# EdgeMax_MCU.net
KiCad netlist of a schematic drawn in Altium Designer
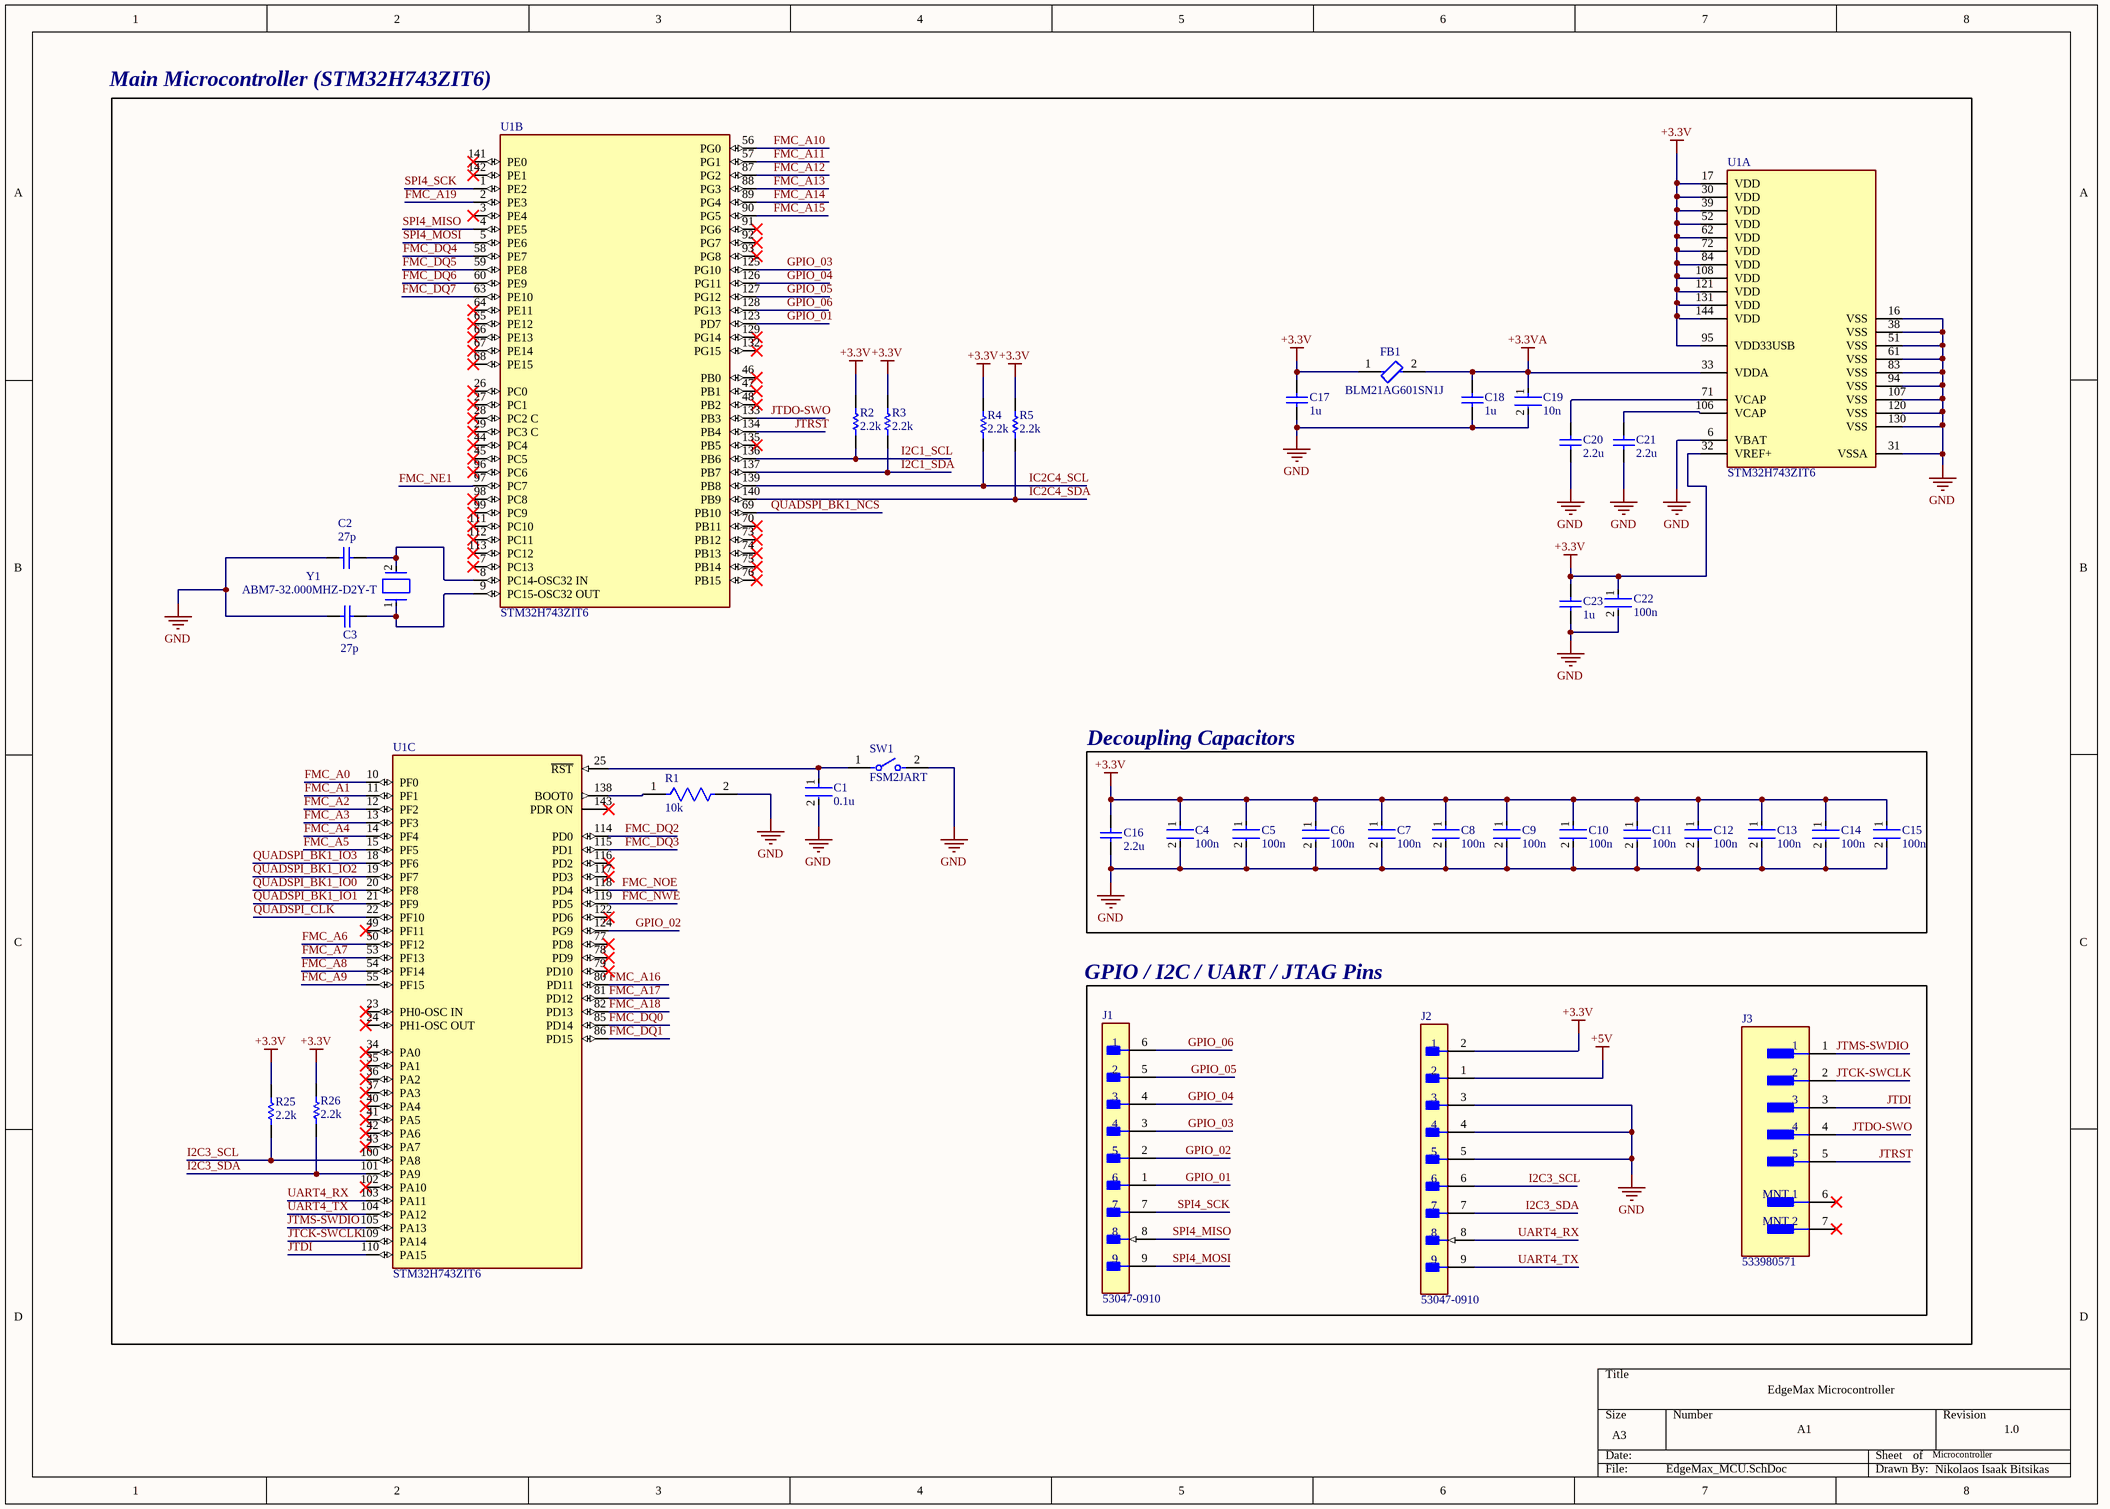
[diagram p0: EdgeMax_MCU.SchDoc]

(export (version "E")
  (design (tool "Eeschema 10.0.6"))
  (components
    (comp (ref "C1")
      (value "0.1u")
      (footprint "FP-C1206C-EB-MFG")
      (description "C1206 68,000 pF X7R 10.00% 50 V")
      (fields
        (field (name "MANUFACTURER") "KEMET")
        (field (name "OCTOPART") "https://octopart.com/c1206c683k5rac-kemet-1491650")
      )
      (libsource (lib "Altium Content Vault") (part "b4654b650e69147ec39a6b967a45e02"))
    )
    (comp (ref "C2")
      (value "27p")
      (footprint "CAPC1005X55X25LL05T10")
      (fields (field (name "PART NUMBER") "GRM1555C1H270JA01D") (field (name "MANUFACTURER") "Murata"))
      (libsource (lib "Altium Content Vault") (part "CAP"))
    )
    (comp (ref "C3")
      (value "27p")
      (footprint "CAPC1005X55X25LL05T10")
      (fields (field (name "PART NUMBER") "GRM1555C1H270JA01D") (field (name "MANUFACTURER") "Murata"))
      (libsource (lib "Altium Content Vault") (part "CAP"))
    )
    (comp (ref "C4")
      (value "100n")
      (footprint "FP-CL10-IPC_A")
      (description "Cap Ceramic 100nF 50V X7R ±10% Pad SMD 0603 +125°C T/R")
      (fields (field (name "VOLTAGE") "50V") (field (name "TOLERANCE") "10%"))
      (libsource (lib "Altium Content Vault") (part "b4654b650e69147ec39a6b967a45e02"))
    )
    (comp (ref "C5")
      (value "100n")
      (footprint "FP-CL10-IPC_A")
      (description "Cap Ceramic 100nF 50V X7R ±10% Pad SMD 0603 +125°C T/R")
      (fields (field (name "VOLTAGE") "50V") (field (name "TOLERANCE") "10%"))
      (libsource (lib "Altium Content Vault") (part "b4654b650e69147ec39a6b967a45e02"))
    )
    (comp (ref "C6")
      (value "100n")
      (footprint "FP-CL10-IPC_A")
      (description "Cap Ceramic 100nF 50V X7R ±10% Pad SMD 0603 +125°C T/R")
      (fields (field (name "VOLTAGE") "50V") (field (name "TOLERANCE") "10%"))
      (libsource (lib "Altium Content Vault") (part "b4654b650e69147ec39a6b967a45e02"))
    )
    (comp (ref "C7")
      (value "100n")
      (footprint "FP-CL10-IPC_A")
      (description "Cap Ceramic 100nF 50V X7R ±10% Pad SMD 0603 +125°C T/R")
      (fields (field (name "VOLTAGE") "50V") (field (name "TOLERANCE") "10%"))
      (libsource (lib "Altium Content Vault") (part "b4654b650e69147ec39a6b967a45e02"))
    )
    (comp (ref "C8")
      (value "100n")
      (footprint "FP-CL10-IPC_A")
      (description "Cap Ceramic 100nF 50V X7R ±10% Pad SMD 0603 +125°C T/R")
      (fields (field (name "VOLTAGE") "50V") (field (name "TOLERANCE") "10%"))
      (libsource (lib "Altium Content Vault") (part "b4654b650e69147ec39a6b967a45e02"))
    )
    (comp (ref "C9")
      (value "100n")
      (footprint "FP-CL10-IPC_A")
      (description "Cap Ceramic 100nF 50V X7R ±10% Pad SMD 0603 +125°C T/R")
      (fields (field (name "VOLTAGE") "50V") (field (name "TOLERANCE") "10%"))
      (libsource (lib "Altium Content Vault") (part "b4654b650e69147ec39a6b967a45e02"))
    )
    (comp (ref "C10")
      (value "100n")
      (footprint "FP-CL10-IPC_A")
      (description "Cap Ceramic 100nF 50V X7R ±10% Pad SMD 0603 +125°C T/R")
      (fields (field (name "VOLTAGE") "50V") (field (name "TOLERANCE") "10%"))
      (libsource (lib "Altium Content Vault") (part "b4654b650e69147ec39a6b967a45e02"))
    )
    (comp (ref "C11")
      (value "100n")
      (footprint "FP-CL10-IPC_A")
      (description "Cap Ceramic 100nF 50V X7R ±10% Pad SMD 0603 +125°C T/R")
      (fields (field (name "VOLTAGE") "50V") (field (name "TOLERANCE") "10%"))
      (libsource (lib "Altium Content Vault") (part "b4654b650e69147ec39a6b967a45e02"))
    )
    (comp (ref "C12")
      (value "100n")
      (footprint "FP-CL10-IPC_A")
      (description "Cap Ceramic 100nF 50V X7R ±10% Pad SMD 0603 +125°C T/R")
      (fields (field (name "VOLTAGE") "50V") (field (name "TOLERANCE") "10%"))
      (libsource (lib "Altium Content Vault") (part "b4654b650e69147ec39a6b967a45e02"))
    )
    (comp (ref "C13")
      (value "100n")
      (footprint "FP-CL10-IPC_A")
      (description "Cap Ceramic 100nF 50V X7R ±10% Pad SMD 0603 +125°C T/R")
      (fields (field (name "VOLTAGE") "50V") (field (name "TOLERANCE") "10%"))
      (libsource (lib "Altium Content Vault") (part "b4654b650e69147ec39a6b967a45e02"))
    )
    (comp (ref "C14")
      (value "100n")
      (footprint "FP-CL10-IPC_A")
      (description "Cap Ceramic 100nF 50V X7R ±10% Pad SMD 0603 +125°C T/R")
      (fields (field (name "VOLTAGE") "50V") (field (name "TOLERANCE") "10%"))
      (libsource (lib "Altium Content Vault") (part "b4654b650e69147ec39a6b967a45e02"))
    )
    (comp (ref "C15")
      (value "100n")
      (footprint "FP-CL10-IPC_A")
      (description "Cap Ceramic 100nF 50V X7R ±10% Pad SMD 0603 +125°C T/R")
      (fields (field (name "VOLTAGE") "50V") (field (name "TOLERANCE") "10%"))
      (libsource (lib "Altium Content Vault") (part "b4654b650e69147ec39a6b967a45e02"))
    )
    (comp (ref "C16")
      (value "2.2u")
      (footprint "CAPC2013X135X50ML10T20")
      (fields (field (name "MANUFACTURER") "Murata") (field (name "PART NUMBER") "GRM21BR71C225KA12L"))
      (libsource (lib "Altium Content Vault") (part "CAP"))
    )
    (comp (ref "C17")
      (value "1u")
      (footprint "CAPC2013X145X50LL20T25")
      (fields (field (name "MANUFACTURER") "Kemet") (field (name "PART NUMBER") "C0805C105K4PACTU"))
      (libsource (lib "Altium Content Vault") (part "CAP"))
    )
    (comp (ref "C18")
      (value "1u")
      (footprint "CAPC2013X145X50LL20T25")
      (fields (field (name "MANUFACTURER") "Kemet") (field (name "PART NUMBER") "C0805C105K4PACTU"))
      (libsource (lib "Altium Content Vault") (part "CAP"))
    )
    (comp (ref "C19")
      (value "10n")
      (footprint "FP-CC0402-MFG")
      (description "CC0402 10 nF X7R 10.00% 16 V")
      (fields
        (field (name "TOLERANCE") "0.1")
        (field (name "OCTOPART") "https://octopart.com/cc0402kpx7r7bb103-yageo-12885102")
      )
      (libsource (lib "Altium Content Vault") (part "11868f565c42a9108669ba33697ecf6"))
    )
    (comp (ref "C20")
      (value "2.2u")
      (footprint "CAPC2013X135X50ML10T20")
      (fields (field (name "MANUFACTURER") "Murata") (field (name "PART NUMBER") "GRM21BR71C225KA12L"))
      (libsource (lib "Altium Content Vault") (part "CAP"))
    )
    (comp (ref "C21")
      (value "2.2u")
      (footprint "CAPC2013X135X50ML10T20")
      (fields (field (name "MANUFACTURER") "Murata") (field (name "PART NUMBER") "GRM21BR71C225KA12L"))
      (libsource (lib "Altium Content Vault") (part "CAP"))
    )
    (comp (ref "C22")
      (value "100n")
      (footprint "FP-CL10-IPC_A")
      (description "Cap Ceramic 100nF 50V X7R ±10% Pad SMD 0603 +125°C T/R")
      (fields (field (name "VOLTAGE") "50V") (field (name "TOLERANCE") "10%"))
      (libsource (lib "Altium Content Vault") (part "b4654b650e69147ec39a6b967a45e02"))
    )
    (comp (ref "C23")
      (value "1u")
      (footprint "CAPC2013X145X50LL20T25")
      (fields (field (name "MANUFACTURER") "Kemet") (field (name "PART NUMBER") "C0805C105K4PACTU"))
      (libsource (lib "Altium Content Vault") (part "CAP"))
    )
    (comp (ref "FB1")
      (value "BLM21AG601SN1J")
      (footprint "FP-BLM21-0_2-t0_85-e0_5-IPC_A")
      (description "Chip Ferrite Bead, 0805, 600Ω @ 100MHz, 0.2Ω, 25%, 700mA")
      (fields (field (name "TOLERANCE") "25%"))
      (libsource (lib "Altium Content Vault") (part "5f30dd21d616792df468990f7003faa"))
    )
    (comp (ref "J1")
      (value "53047-0910")
      (footprint "FP-53047-0910-MFG")
      (description "CONN HEADER VERT 9POS 1.25MM")
      (libsource (lib "") (part "dac6df820644cf490af5575b4ac23d9_1"))
    )
    (comp (ref "J2")
      (value "53047-0910")
      (footprint "FP-53047-0910-MFG")
      (description "CONN HEADER VERT 9POS 1.25MM")
      (libsource (lib "Altium Content Vault") (part "dac6df820644cf490af5575b4ac23d9"))
    )
    (comp (ref "J3")
      (value "533980571")
      (footprint "FP-533980571-MFG")
      (description "CONN HEADER SMD 5POS 1.25MM")
      (fields
        (field (name "MANUFACTURER") "Molex")
        (field (name "OCTOPART") "https://octopart.com/53398-0571-molex-655292")
      )
      (libsource (lib "Altium Content Vault") (part "6850237a4f4b29aa870910a3747ee34"))
    )
    (comp (ref "R1")
      (value "10k")
      (footprint "FP-AC0603-MFG")
      (description "RES 10KΩ 1.00% 0.1W 0603")
      (fields (field (name "TOLERANCE") "1%"))
      (libsource (lib "Altium Content Vault") (part "1029c3af85768c4190bb7ad29bc67b5"))
    )
    (comp (ref "R2")
      (value "2.2k")
      (footprint "RESC1005X40X25LL05T05")
      (fields (field (name "MANUFACTURER") "Panasonic"))
      (libsource (lib "Altium Content Vault") (part "RES-2"))
    )
    (comp (ref "R3")
      (value "2.2k")
      (footprint "RESC1005X40X25LL05T05")
      (fields (field (name "MANUFACTURER") "Panasonic"))
      (libsource (lib "Altium Content Vault") (part "RES-2"))
    )
    (comp (ref "R4")
      (value "2.2k")
      (footprint "RESC1005X40X25LL05T05")
      (fields (field (name "MANUFACTURER") "Panasonic"))
      (libsource (lib "Altium Content Vault") (part "RES-2"))
    )
    (comp (ref "R5")
      (value "2.2k")
      (footprint "RESC1005X40X25LL05T05")
      (fields (field (name "MANUFACTURER") "Panasonic"))
      (libsource (lib "Altium Content Vault") (part "RES-2"))
    )
    (comp (ref "R25")
      (value "2.2k")
      (footprint "RESC1005X40X25LL05T05")
      (fields (field (name "MANUFACTURER") "Panasonic"))
      (libsource (lib "Altium Content Vault") (part "RES-2"))
    )
    (comp (ref "R26")
      (value "2.2k")
      (footprint "RESC1005X40X25LL05T05")
      (fields (field (name "MANUFACTURER") "Panasonic"))
      (libsource (lib "Altium Content Vault") (part "RES-2"))
    )
    (comp (ref "SW1")
      (value "FSM2JART")
      (footprint "FP-FSM2JART-MFG")
      (description "SWITCH TACTILE SPST-NO 0.05A 12V")
      (libsource (lib "Altium Content Vault") (part "bb27bde45df87f1f469753f287ef5ae"))
    )
    (comp (ref "U1")
      (value "STM32H743ZIT6")
      (footprint "FP-LQFP144-1A-MFG")
      (description "IC MCU 32BIT 2MB FLASH 144LQFP")
      (fields
        (field (name "MANUFACTURER") "STMicroelectronics")
        (field (name "OCTOPART") "https://octopart.com/stm32h743zit6-stmicroelectronics-76372529")
      )
      (libsource (lib "") (part "4977c5c7f8d170b58ef15f889e64ba1_2"))
    )
    (comp (ref "Y1")
      (value "ABM7-32.000MHZ-D2Y-T")
      (footprint "FP-ABM7-MFG")
      (description "Crystal 32MHz ±20ppm 18pF SMD-2 6mm x 3.5mm")
      (fields (field (name "TOLERANCE") "20ppm"))
      (libsource (lib "Altium Content Vault") (part "c23a69dc6c9e2f18f2079038eb95dd1"))
    )
  )
  (nets
    (net (code "1") (name "+3.3V") (class "Default")
      (node (ref "C10") (pin "1") (pinfunction "1_1") (pintype "passive"))
      (node (ref "C11") (pin "1") (pinfunction "1_1") (pintype "passive"))
      (node (ref "C12") (pin "1") (pinfunction "1_1") (pintype "passive"))
      (node (ref "C13") (pin "1") (pinfunction "1_1") (pintype "passive"))
      (node (ref "C14") (pin "1") (pinfunction "1_1") (pintype "passive"))
      (node (ref "C15") (pin "1") (pinfunction "1_1") (pintype "passive"))
      (node (ref "C16") (pin "2") (pinfunction "2_2") (pintype "passive"))
      (node (ref "C17") (pin "2") (pinfunction "2_2") (pintype "passive"))
      (node (ref "C22") (pin "1") (pinfunction "1_1") (pintype "passive"))
      (node (ref "C23") (pin "2") (pinfunction "2_2") (pintype "passive"))
      (node (ref "C4") (pin "1") (pinfunction "1_1") (pintype "passive"))
      (node (ref "C5") (pin "1") (pinfunction "1_1") (pintype "passive"))
      (node (ref "C6") (pin "1") (pinfunction "1_1") (pintype "passive"))
      (node (ref "C7") (pin "1") (pinfunction "1_1") (pintype "passive"))
      (node (ref "C8") (pin "1") (pinfunction "1_1") (pintype "passive"))
      (node (ref "C9") (pin "1") (pinfunction "1_1") (pintype "passive"))
      (node (ref "FB1") (pin "1") (pinfunction "1_1") (pintype "passive"))
      (node (ref "J2") (pin "2") (pinfunction "2_2") (pintype "passive"))
      (node (ref "R2") (pin "2") (pinfunction "2_2") (pintype "passive"))
      (node (ref "R25") (pin "2") (pinfunction "2_2") (pintype "passive"))
      (node (ref "R26") (pin "2") (pinfunction "2_2") (pintype "passive"))
      (node (ref "R3") (pin "2") (pinfunction "2_2") (pintype "passive"))
      (node (ref "R4") (pin "2") (pinfunction "2_2") (pintype "passive"))
      (node (ref "R5") (pin "2") (pinfunction "2_2") (pintype "passive"))
      (node (ref "U1") (pin "108") (pinfunction "VDD_108") (pintype "power_in"))
      (node (ref "U1") (pin "121") (pinfunction "VDD_121") (pintype "power_in"))
      (node (ref "U1") (pin "131") (pinfunction "VDD_131") (pintype "power_in"))
      (node (ref "U1") (pin "144") (pinfunction "VDD_144") (pintype "power_in"))
      (node (ref "U1") (pin "17") (pinfunction "VDD_17") (pintype "power_in"))
      (node (ref "U1") (pin "30") (pinfunction "VDD_30") (pintype "power_in"))
      (node (ref "U1") (pin "32") (pinfunction "VREF+_32") (pintype "power_in"))
      (node (ref "U1") (pin "39") (pinfunction "VDD_39") (pintype "power_in"))
      (node (ref "U1") (pin "52") (pinfunction "VDD_52") (pintype "power_in"))
      (node (ref "U1") (pin "62") (pinfunction "VDD_62") (pintype "power_in"))
      (node (ref "U1") (pin "72") (pinfunction "VDD_72") (pintype "power_in"))
      (node (ref "U1") (pin "84") (pinfunction "VDD_84") (pintype "power_in"))
      (node (ref "U1") (pin "95") (pinfunction "VDD33USB_95") (pintype "power_in"))
    )
    (net (code "2") (name "+3.3VA") (class "Default")
      (node (ref "C18") (pin "2") (pinfunction "2_2") (pintype "passive"))
      (node (ref "C19") (pin "1") (pinfunction "1_1") (pintype "passive"))
      (node (ref "FB1") (pin "2") (pinfunction "2_2") (pintype "passive"))
      (node (ref "U1") (pin "33") (pinfunction "VDDA_33") (pintype "power_in"))
    )
    (net (code "3") (name "+5V") (class "Default")
      (node (ref "J2") (pin "1") (pinfunction "1_1") (pintype "passive"))
    )
    (net (code "4") (name "/FMC_A0") (class "Default")
      (node (ref "U1") (pin "10") (pinfunction "PF0_10") (pintype "bidirectional"))
    )
    (net (code "5") (name "/FMC_A1") (class "Default")
      (node (ref "U1") (pin "11") (pinfunction "PF1_11") (pintype "bidirectional"))
    )
    (net (code "6") (name "/FMC_A2") (class "Default")
      (node (ref "U1") (pin "12") (pinfunction "PF2_12") (pintype "bidirectional"))
    )
    (net (code "7") (name "/FMC_A3") (class "Default")
      (node (ref "U1") (pin "13") (pinfunction "PF3_13") (pintype "bidirectional"))
    )
    (net (code "8") (name "/FMC_A4") (class "Default")
      (node (ref "U1") (pin "14") (pinfunction "PF4_14") (pintype "bidirectional"))
    )
    (net (code "9") (name "/FMC_A5") (class "Default")
      (node (ref "U1") (pin "15") (pinfunction "PF5_15") (pintype "bidirectional"))
    )
    (net (code "10") (name "/FMC_A6") (class "Default")
      (node (ref "U1") (pin "50") (pinfunction "PF12_50") (pintype "bidirectional"))
    )
    (net (code "11") (name "/FMC_A7") (class "Default")
      (node (ref "U1") (pin "53") (pinfunction "PF13_53") (pintype "bidirectional"))
    )
    (net (code "12") (name "/FMC_A8") (class "Default")
      (node (ref "U1") (pin "54") (pinfunction "PF14_54") (pintype "bidirectional"))
    )
    (net (code "13") (name "/FMC_A9") (class "Default")
      (node (ref "U1") (pin "55") (pinfunction "PF15_55") (pintype "bidirectional"))
    )
    (net (code "14") (name "/FMC_A10") (class "Default")
      (node (ref "U1") (pin "56") (pinfunction "PG0_56") (pintype "bidirectional"))
    )
    (net (code "15") (name "/FMC_A11") (class "Default")
      (node (ref "U1") (pin "57") (pinfunction "PG1_57") (pintype "bidirectional"))
    )
    (net (code "16") (name "/FMC_A12") (class "Default")
      (node (ref "U1") (pin "87") (pinfunction "PG2_87") (pintype "bidirectional"))
    )
    (net (code "17") (name "/FMC_A13") (class "Default")
      (node (ref "U1") (pin "88") (pinfunction "PG3_88") (pintype "bidirectional"))
    )
    (net (code "18") (name "/FMC_A14") (class "Default")
      (node (ref "U1") (pin "89") (pinfunction "PG4_89") (pintype "bidirectional"))
    )
    (net (code "19") (name "/FMC_A15") (class "Default")
      (node (ref "U1") (pin "90") (pinfunction "PG5_90") (pintype "bidirectional"))
    )
    (net (code "20") (name "/FMC_A16") (class "Default")
      (node (ref "U1") (pin "80") (pinfunction "PD11_80") (pintype "bidirectional"))
    )
    (net (code "21") (name "/FMC_A17") (class "Default")
      (node (ref "U1") (pin "81") (pinfunction "PD12_81") (pintype "bidirectional"))
    )
    (net (code "22") (name "/FMC_A18") (class "Default")
      (node (ref "U1") (pin "82") (pinfunction "PD13_82") (pintype "bidirectional"))
    )
    (net (code "23") (name "/FMC_A19") (class "Default")
      (node (ref "U1") (pin "2") (pinfunction "PE3_2") (pintype "bidirectional"))
    )
    (net (code "24") (name "/FMC_DQ0") (class "Default")
      (node (ref "U1") (pin "85") (pinfunction "PD14_85") (pintype "bidirectional"))
    )
    (net (code "25") (name "/FMC_DQ1") (class "Default")
      (node (ref "U1") (pin "86") (pinfunction "PD15_86") (pintype "bidirectional"))
    )
    (net (code "26") (name "/FMC_DQ2") (class "Default")
      (node (ref "U1") (pin "114") (pinfunction "PD0_114") (pintype "bidirectional"))
    )
    (net (code "27") (name "/FMC_DQ3") (class "Default")
      (node (ref "U1") (pin "115") (pinfunction "PD1_115") (pintype "bidirectional"))
    )
    (net (code "28") (name "/FMC_DQ4") (class "Default")
      (node (ref "U1") (pin "58") (pinfunction "PE7_58") (pintype "bidirectional"))
    )
    (net (code "29") (name "/FMC_DQ5") (class "Default")
      (node (ref "U1") (pin "59") (pinfunction "PE8_59") (pintype "bidirectional"))
    )
    (net (code "30") (name "/FMC_DQ6") (class "Default")
      (node (ref "U1") (pin "60") (pinfunction "PE9_60") (pintype "bidirectional"))
    )
    (net (code "31") (name "/FMC_DQ7") (class "Default")
      (node (ref "U1") (pin "63") (pinfunction "PE10_63") (pintype "bidirectional"))
    )
    (net (code "32") (name "/FMC_NOE") (class "Default")
      (node (ref "U1") (pin "118") (pinfunction "PD4_118") (pintype "bidirectional"))
    )
    (net (code "33") (name "/FMC_NWE") (class "Default")
      (node (ref "U1") (pin "119") (pinfunction "PD5_119") (pintype "bidirectional"))
    )
    (net (code "34") (name "/FMC_ΝΕ1") (class "Default")
      (node (ref "U1") (pin "97") (pinfunction "PC7_97") (pintype "bidirectional"))
    )
    (net (code "35") (name "/GPIO_01") (class "Default")
      (node (ref "J1") (pin "1") (pinfunction "1_1") (pintype "passive"))
      (node (ref "U1") (pin "123") (pinfunction "PD7_123") (pintype "bidirectional"))
    )
    (net (code "36") (name "/GPIO_02") (class "Default")
      (node (ref "J1") (pin "2") (pinfunction "2_2") (pintype "passive"))
      (node (ref "U1") (pin "124") (pinfunction "PG9_124") (pintype "bidirectional"))
    )
    (net (code "37") (name "/GPIO_03") (class "Default")
      (node (ref "J1") (pin "3") (pinfunction "3_3") (pintype "passive"))
      (node (ref "U1") (pin "125") (pinfunction "PG10_125") (pintype "bidirectional"))
    )
    (net (code "38") (name "/GPIO_04") (class "Default")
      (node (ref "J1") (pin "4") (pinfunction "4_4") (pintype "passive"))
      (node (ref "U1") (pin "126") (pinfunction "PG11_126") (pintype "bidirectional"))
    )
    (net (code "39") (name "/GPIO_05") (class "Default")
      (node (ref "J1") (pin "5") (pinfunction "5_5") (pintype "passive"))
      (node (ref "U1") (pin "127") (pinfunction "PG12_127") (pintype "bidirectional"))
    )
    (net (code "40") (name "/GPIO_06") (class "Default")
      (node (ref "J1") (pin "6") (pinfunction "6_6") (pintype "passive"))
      (node (ref "U1") (pin "128") (pinfunction "PG13_128") (pintype "bidirectional"))
    )
    (net (code "41") (name "/I2C1_SCL") (class "Default")
      (node (ref "R2") (pin "1") (pinfunction "1_1") (pintype "passive"))
      (node (ref "U1") (pin "136") (pinfunction "PB6_136") (pintype "bidirectional"))
    )
    (net (code "42") (name "/I2C1_SDA") (class "Default")
      (node (ref "R3") (pin "1") (pinfunction "1_1") (pintype "passive"))
      (node (ref "U1") (pin "137") (pinfunction "PB7_137") (pintype "bidirectional"))
    )
    (net (code "43") (name "/I2C3_SCL") (class "Default")
      (node (ref "J2") (pin "6") (pinfunction "6_6") (pintype "passive"))
      (node (ref "R25") (pin "1") (pinfunction "1_1") (pintype "passive"))
      (node (ref "U1") (pin "100") (pinfunction "PA8_100") (pintype "bidirectional"))
    )
    (net (code "44") (name "/I2C3_SDA") (class "Default")
      (node (ref "J2") (pin "7") (pinfunction "7_7") (pintype "passive"))
      (node (ref "R26") (pin "1") (pinfunction "1_1") (pintype "passive"))
      (node (ref "U1") (pin "101") (pinfunction "PA9_101") (pintype "bidirectional"))
    )
    (net (code "45") (name "/IC2C4_SCL") (class "Default")
      (node (ref "R4") (pin "1") (pinfunction "1_1") (pintype "passive"))
      (node (ref "U1") (pin "139") (pinfunction "PB8_139") (pintype "bidirectional"))
    )
    (net (code "46") (name "/IC2C4_SDA") (class "Default")
      (node (ref "R5") (pin "1") (pinfunction "1_1") (pintype "passive"))
      (node (ref "U1") (pin "140") (pinfunction "PB9_140") (pintype "bidirectional"))
    )
    (net (code "47") (name "/JTCK-SWCLK") (class "Default")
      (node (ref "J3") (pin "2") (pinfunction "2_2") (pintype "passive"))
      (node (ref "U1") (pin "109") (pinfunction "PA14_109") (pintype "bidirectional"))
    )
    (net (code "48") (name "/JTDI") (class "Default")
      (node (ref "J3") (pin "3") (pinfunction "3_3") (pintype "passive"))
      (node (ref "U1") (pin "110") (pinfunction "PA15_110") (pintype "bidirectional"))
    )
    (net (code "49") (name "/JTDO-SWO") (class "Default")
      (node (ref "J3") (pin "4") (pinfunction "4_4") (pintype "passive"))
      (node (ref "U1") (pin "133") (pinfunction "PB3_133") (pintype "bidirectional"))
    )
    (net (code "50") (name "/JTMS-SWDIO") (class "Default")
      (node (ref "J3") (pin "1") (pinfunction "1_1") (pintype "passive"))
      (node (ref "U1") (pin "105") (pinfunction "PA13_105") (pintype "bidirectional"))
    )
    (net (code "51") (name "/JTRST") (class "Default")
      (node (ref "J3") (pin "5") (pinfunction "5_5") (pintype "passive"))
      (node (ref "U1") (pin "134") (pinfunction "PB4_134") (pintype "bidirectional"))
    )
    (net (code "52") (name "/QUADSPI_BK1_IO0") (class "Default")
      (node (ref "U1") (pin "20") (pinfunction "PF8_20") (pintype "bidirectional"))
    )
    (net (code "53") (name "/QUADSPI_BK1_IO1") (class "Default")
      (node (ref "U1") (pin "21") (pinfunction "PF9_21") (pintype "bidirectional"))
    )
    (net (code "54") (name "/QUADSPI_BK1_IO2") (class "Default")
      (node (ref "U1") (pin "19") (pinfunction "PF7_19") (pintype "bidirectional"))
    )
    (net (code "55") (name "/QUADSPI_BK1_IO3") (class "Default")
      (node (ref "U1") (pin "18") (pinfunction "PF6_18") (pintype "bidirectional"))
    )
    (net (code "56") (name "/QUADSPI_BK1_NCS") (class "Default")
      (node (ref "U1") (pin "69") (pinfunction "PB10_69") (pintype "bidirectional"))
    )
    (net (code "57") (name "/QUADSPI_CLK") (class "Default")
      (node (ref "U1") (pin "22") (pinfunction "PF10_22") (pintype "bidirectional"))
    )
    (net (code "58") (name "/SPI4_MISO") (class "Default")
      (node (ref "J1") (pin "8") (pinfunction "8_8") (pintype "input"))
      (node (ref "U1") (pin "4") (pinfunction "PE5_4") (pintype "bidirectional"))
    )
    (net (code "59") (name "/SPI4_MOSI") (class "Default")
      (node (ref "J1") (pin "9") (pinfunction "9_9") (pintype "passive"))
      (node (ref "U1") (pin "5") (pinfunction "PE6_5") (pintype "bidirectional"))
    )
    (net (code "60") (name "/SPI4_SCK") (class "Default")
      (node (ref "J1") (pin "7") (pinfunction "7_7") (pintype "passive"))
      (node (ref "U1") (pin "1") (pinfunction "PE2_1") (pintype "bidirectional"))
    )
    (net (code "61") (name "/UART4_RX") (class "Default")
      (node (ref "J2") (pin "8") (pinfunction "8_8") (pintype "input"))
      (node (ref "U1") (pin "103") (pinfunction "PA11_103") (pintype "bidirectional"))
    )
    (net (code "62") (name "/UART4_TX") (class "Default")
      (node (ref "J2") (pin "9") (pinfunction "9_9") (pintype "passive"))
      (node (ref "U1") (pin "104") (pinfunction "PA12_104") (pintype "bidirectional"))
    )
    (net (code "63") (name "GND") (class "Default")
      (node (ref "C1") (pin "2") (pinfunction "2_2") (pintype "passive"))
      (node (ref "C10") (pin "2") (pinfunction "2_2") (pintype "passive"))
      (node (ref "C11") (pin "2") (pinfunction "2_2") (pintype "passive"))
      (node (ref "C12") (pin "2") (pinfunction "2_2") (pintype "passive"))
      (node (ref "C13") (pin "2") (pinfunction "2_2") (pintype "passive"))
      (node (ref "C14") (pin "2") (pinfunction "2_2") (pintype "passive"))
      (node (ref "C15") (pin "2") (pinfunction "2_2") (pintype "passive"))
      (node (ref "C16") (pin "1") (pinfunction "1_1") (pintype "passive"))
      (node (ref "C17") (pin "1") (pinfunction "1_1") (pintype "passive"))
      (node (ref "C18") (pin "1") (pinfunction "1_1") (pintype "passive"))
      (node (ref "C19") (pin "2") (pinfunction "2_2") (pintype "passive"))
      (node (ref "C2") (pin "2") (pinfunction "2_2") (pintype "passive"))
      (node (ref "C20") (pin "1") (pinfunction "1_1") (pintype "passive"))
      (node (ref "C21") (pin "1") (pinfunction "1_1") (pintype "passive"))
      (node (ref "C22") (pin "2") (pinfunction "2_2") (pintype "passive"))
      (node (ref "C23") (pin "1") (pinfunction "1_1") (pintype "passive"))
      (node (ref "C3") (pin "1") (pinfunction "1_1") (pintype "passive"))
      (node (ref "C4") (pin "2") (pinfunction "2_2") (pintype "passive"))
      (node (ref "C5") (pin "2") (pinfunction "2_2") (pintype "passive"))
      (node (ref "C6") (pin "2") (pinfunction "2_2") (pintype "passive"))
      (node (ref "C7") (pin "2") (pinfunction "2_2") (pintype "passive"))
      (node (ref "C8") (pin "2") (pinfunction "2_2") (pintype "passive"))
      (node (ref "C9") (pin "2") (pinfunction "2_2") (pintype "passive"))
      (node (ref "J2") (pin "3") (pinfunction "3_3") (pintype "passive"))
      (node (ref "J2") (pin "4") (pinfunction "4_4") (pintype "passive"))
      (node (ref "J2") (pin "5") (pinfunction "5_5") (pintype "passive"))
      (node (ref "R1") (pin "2") (pinfunction "2_2") (pintype "passive"))
      (node (ref "SW1") (pin "2") (pinfunction "2_2") (pintype "passive"))
      (node (ref "U1") (pin "107") (pinfunction "VSS_107") (pintype "power_in"))
      (node (ref "U1") (pin "120") (pinfunction "VSS_120") (pintype "power_in"))
      (node (ref "U1") (pin "130") (pinfunction "VSS_130") (pintype "power_in"))
      (node (ref "U1") (pin "16") (pinfunction "VSS_16") (pintype "power_in"))
      (node (ref "U1") (pin "31") (pinfunction "VSSA_31") (pintype "power_in"))
      (node (ref "U1") (pin "38") (pinfunction "VSS_38") (pintype "power_in"))
      (node (ref "U1") (pin "51") (pinfunction "VSS_51") (pintype "power_in"))
      (node (ref "U1") (pin "6") (pinfunction "VBAT_6") (pintype "power_in"))
      (node (ref "U1") (pin "61") (pinfunction "VSS_61") (pintype "power_in"))
      (node (ref "U1") (pin "83") (pinfunction "VSS_83") (pintype "power_in"))
      (node (ref "U1") (pin "94") (pinfunction "VSS_94") (pintype "power_in"))
    )
    (net (code "64") (name "Net-(C20-Pad2)") (class "Default")
      (node (ref "C20") (pin "2") (pinfunction "2_2") (pintype "passive"))
      (node (ref "U1") (pin "71") (pinfunction "VCAP_71") (pintype "power_in"))
    )
    (net (code "65") (name "Net-(C21-Pad2)") (class "Default")
      (node (ref "C21") (pin "2") (pinfunction "2_2") (pintype "passive"))
      (node (ref "U1") (pin "106") (pinfunction "VCAP_106") (pintype "power_in"))
    )
    (net (code "66") (name "Net-(U1B-PC14-OSC32_IN)") (class "Default")
      (node (ref "C2") (pin "1") (pinfunction "1_1") (pintype "passive"))
      (node (ref "U1") (pin "8") (pinfunction "PC14-OSC32_IN_8") (pintype "bidirectional"))
      (node (ref "Y1") (pin "2") (pinfunction "2_2") (pintype "passive"))
    )
    (net (code "67") (name "Net-(U1B-PC15-OSC32_OUT)") (class "Default")
      (node (ref "C3") (pin "2") (pinfunction "2_2") (pintype "passive"))
      (node (ref "U1") (pin "9") (pinfunction "PC15-OSC32_OUT_9") (pintype "bidirectional"))
      (node (ref "Y1") (pin "1") (pinfunction "1_1") (pintype "passive"))
    )
    (net (code "68") (name "Net-(U1C-BOOT0)") (class "Default")
      (node (ref "R1") (pin "1") (pinfunction "1_1") (pintype "passive"))
      (node (ref "U1") (pin "138") (pinfunction "BOOT0_138") (pintype "output"))
    )
    (net (code "69") (name "Net-(U1C-~{RST})") (class "Default")
      (node (ref "C1") (pin "1") (pinfunction "1_1") (pintype "passive"))
      (node (ref "SW1") (pin "1") (pinfunction "1_1") (pintype "passive"))
      (node (ref "U1") (pin "25") (pinfunction "~{RST}_25") (pintype "input"))
    )
    (net (code "70") (name "unconnected-(J3-MNT_1-Pad6)") (class "Default")
      (node (ref "J3") (pin "6") (pinfunction "MNT_1_6") (pintype "passive+no_connect"))
    )
    (net (code "71") (name "unconnected-(J3-MNT_2-Pad7)") (class "Default")
      (node (ref "J3") (pin "7") (pinfunction "MNT_2_7") (pintype "passive+no_connect"))
    )
    (net (code "72") (name "unconnected-(U1B-PB0-Pad46)") (class "Default")
      (node (ref "U1") (pin "46") (pinfunction "PB0_46") (pintype "bidirectional+no_connect"))
    )
    (net (code "73") (name "unconnected-(U1B-PB1-Pad47)") (class "Default")
      (node (ref "U1") (pin "47") (pinfunction "PB1_47") (pintype "bidirectional+no_connect"))
    )
    (net (code "74") (name "unconnected-(U1B-PB2-Pad48)") (class "Default")
      (node (ref "U1") (pin "48") (pinfunction "PB2_48") (pintype "bidirectional+no_connect"))
    )
    (net (code "75") (name "unconnected-(U1B-PB5-Pad135)") (class "Default")
      (node (ref "U1") (pin "135") (pinfunction "PB5_135") (pintype "bidirectional+no_connect"))
    )
    (net (code "76") (name "unconnected-(U1B-PB11-Pad70)") (class "Default")
      (node (ref "U1") (pin "70") (pinfunction "PB11_70") (pintype "bidirectional+no_connect"))
    )
    (net (code "77") (name "unconnected-(U1B-PB12-Pad73)") (class "Default")
      (node (ref "U1") (pin "73") (pinfunction "PB12_73") (pintype "bidirectional+no_connect"))
    )
    (net (code "78") (name "unconnected-(U1B-PB13-Pad74)") (class "Default")
      (node (ref "U1") (pin "74") (pinfunction "PB13_74") (pintype "bidirectional+no_connect"))
    )
    (net (code "79") (name "unconnected-(U1B-PB14-Pad75)") (class "Default")
      (node (ref "U1") (pin "75") (pinfunction "PB14_75") (pintype "bidirectional+no_connect"))
    )
    (net (code "80") (name "unconnected-(U1B-PB15-Pad76)") (class "Default")
      (node (ref "U1") (pin "76") (pinfunction "PB15_76") (pintype "bidirectional+no_connect"))
    )
    (net (code "81") (name "unconnected-(U1B-PC0-Pad26)") (class "Default")
      (node (ref "U1") (pin "26") (pinfunction "PC0_26") (pintype "bidirectional+no_connect"))
    )
    (net (code "82") (name "unconnected-(U1B-PC1-Pad27)") (class "Default")
      (node (ref "U1") (pin "27") (pinfunction "PC1_27") (pintype "bidirectional+no_connect"))
    )
    (net (code "83") (name "unconnected-(U1B-PC2_C-Pad28)") (class "Default")
      (node (ref "U1") (pin "28") (pinfunction "PC2_C_28") (pintype "bidirectional+no_connect"))
    )
    (net (code "84") (name "unconnected-(U1B-PC3_C-Pad29)") (class "Default")
      (node (ref "U1") (pin "29") (pinfunction "PC3_C_29") (pintype "bidirectional+no_connect"))
    )
    (net (code "85") (name "unconnected-(U1B-PC4-Pad44)") (class "Default")
      (node (ref "U1") (pin "44") (pinfunction "PC4_44") (pintype "bidirectional+no_connect"))
    )
    (net (code "86") (name "unconnected-(U1B-PC5-Pad45)") (class "Default")
      (node (ref "U1") (pin "45") (pinfunction "PC5_45") (pintype "bidirectional+no_connect"))
    )
    (net (code "87") (name "unconnected-(U1B-PC6-Pad96)") (class "Default")
      (node (ref "U1") (pin "96") (pinfunction "PC6_96") (pintype "bidirectional+no_connect"))
    )
    (net (code "88") (name "unconnected-(U1B-PC8-Pad98)") (class "Default")
      (node (ref "U1") (pin "98") (pinfunction "PC8_98") (pintype "bidirectional+no_connect"))
    )
    (net (code "89") (name "unconnected-(U1B-PC9-Pad99)") (class "Default")
      (node (ref "U1") (pin "99") (pinfunction "PC9_99") (pintype "bidirectional+no_connect"))
    )
    (net (code "90") (name "unconnected-(U1B-PC10-Pad111)") (class "Default")
      (node (ref "U1") (pin "111") (pinfunction "PC10_111") (pintype "bidirectional+no_connect"))
    )
    (net (code "91") (name "unconnected-(U1B-PC11-Pad112)") (class "Default")
      (node (ref "U1") (pin "112") (pinfunction "PC11_112") (pintype "bidirectional+no_connect"))
    )
    (net (code "92") (name "unconnected-(U1B-PC12-Pad113)") (class "Default")
      (node (ref "U1") (pin "113") (pinfunction "PC12_113") (pintype "bidirectional+no_connect"))
    )
    (net (code "93") (name "unconnected-(U1B-PC13-Pad7)") (class "Default")
      (node (ref "U1") (pin "7") (pinfunction "PC13_7") (pintype "bidirectional+no_connect"))
    )
    (net (code "94") (name "unconnected-(U1B-PE0-Pad141)") (class "Default")
      (node (ref "U1") (pin "141") (pinfunction "PE0_141") (pintype "bidirectional+no_connect"))
    )
    (net (code "95") (name "unconnected-(U1B-PE1-Pad142)") (class "Default")
      (node (ref "U1") (pin "142") (pinfunction "PE1_142") (pintype "bidirectional+no_connect"))
    )
    (net (code "96") (name "unconnected-(U1B-PE4-Pad3)") (class "Default")
      (node (ref "U1") (pin "3") (pinfunction "PE4_3") (pintype "bidirectional+no_connect"))
    )
    (net (code "97") (name "unconnected-(U1B-PE11-Pad64)") (class "Default")
      (node (ref "U1") (pin "64") (pinfunction "PE11_64") (pintype "bidirectional+no_connect"))
    )
    (net (code "98") (name "unconnected-(U1B-PE12-Pad65)") (class "Default")
      (node (ref "U1") (pin "65") (pinfunction "PE12_65") (pintype "bidirectional+no_connect"))
    )
    (net (code "99") (name "unconnected-(U1B-PE13-Pad66)") (class "Default")
      (node (ref "U1") (pin "66") (pinfunction "PE13_66") (pintype "bidirectional+no_connect"))
    )
    (net (code "100") (name "unconnected-(U1B-PE14-Pad67)") (class "Default")
      (node (ref "U1") (pin "67") (pinfunction "PE14_67") (pintype "bidirectional+no_connect"))
    )
    (net (code "101") (name "unconnected-(U1B-PE15-Pad68)") (class "Default")
      (node (ref "U1") (pin "68") (pinfunction "PE15_68") (pintype "bidirectional+no_connect"))
    )
    (net (code "102") (name "unconnected-(U1B-PG6-Pad91)") (class "Default")
      (node (ref "U1") (pin "91") (pinfunction "PG6_91") (pintype "bidirectional+no_connect"))
    )
    (net (code "103") (name "unconnected-(U1B-PG7-Pad92)") (class "Default")
      (node (ref "U1") (pin "92") (pinfunction "PG7_92") (pintype "bidirectional+no_connect"))
    )
    (net (code "104") (name "unconnected-(U1B-PG8-Pad93)") (class "Default")
      (node (ref "U1") (pin "93") (pinfunction "PG8_93") (pintype "bidirectional+no_connect"))
    )
    (net (code "105") (name "unconnected-(U1B-PG14-Pad129)") (class "Default")
      (node (ref "U1") (pin "129") (pinfunction "PG14_129") (pintype "bidirectional+no_connect"))
    )
    (net (code "106") (name "unconnected-(U1B-PG15-Pad132)") (class "Default")
      (node (ref "U1") (pin "132") (pinfunction "PG15_132") (pintype "bidirectional+no_connect"))
    )
    (net (code "107") (name "unconnected-(U1C-PA0-Pad34)") (class "Default")
      (node (ref "U1") (pin "34") (pinfunction "PA0_34") (pintype "bidirectional+no_connect"))
    )
    (net (code "108") (name "unconnected-(U1C-PA1-Pad35)") (class "Default")
      (node (ref "U1") (pin "35") (pinfunction "PA1_35") (pintype "bidirectional+no_connect"))
    )
    (net (code "109") (name "unconnected-(U1C-PA2-Pad36)") (class "Default")
      (node (ref "U1") (pin "36") (pinfunction "PA2_36") (pintype "bidirectional+no_connect"))
    )
    (net (code "110") (name "unconnected-(U1C-PA3-Pad37)") (class "Default")
      (node (ref "U1") (pin "37") (pinfunction "PA3_37") (pintype "bidirectional+no_connect"))
    )
    (net (code "111") (name "unconnected-(U1C-PA4-Pad40)") (class "Default")
      (node (ref "U1") (pin "40") (pinfunction "PA4_40") (pintype "bidirectional+no_connect"))
    )
    (net (code "112") (name "unconnected-(U1C-PA5-Pad41)") (class "Default")
      (node (ref "U1") (pin "41") (pinfunction "PA5_41") (pintype "bidirectional+no_connect"))
    )
    (net (code "113") (name "unconnected-(U1C-PA6-Pad42)") (class "Default")
      (node (ref "U1") (pin "42") (pinfunction "PA6_42") (pintype "bidirectional+no_connect"))
    )
    (net (code "114") (name "unconnected-(U1C-PA7-Pad43)") (class "Default")
      (node (ref "U1") (pin "43") (pinfunction "PA7_43") (pintype "bidirectional+no_connect"))
    )
    (net (code "115") (name "unconnected-(U1C-PA10-Pad102)") (class "Default")
      (node (ref "U1") (pin "102") (pinfunction "PA10_102") (pintype "bidirectional+no_connect"))
    )
    (net (code "116") (name "unconnected-(U1C-PD2-Pad116)") (class "Default")
      (node (ref "U1") (pin "116") (pinfunction "PD2_116") (pintype "bidirectional+no_connect"))
    )
    (net (code "117") (name "unconnected-(U1C-PD3-Pad117)") (class "Default")
      (node (ref "U1") (pin "117") (pinfunction "PD3_117") (pintype "bidirectional+no_connect"))
    )
    (net (code "118") (name "unconnected-(U1C-PD6-Pad122)") (class "Default")
      (node (ref "U1") (pin "122") (pinfunction "PD6_122") (pintype "bidirectional+no_connect"))
    )
    (net (code "119") (name "unconnected-(U1C-PD8-Pad77)") (class "Default")
      (node (ref "U1") (pin "77") (pinfunction "PD8_77") (pintype "bidirectional+no_connect"))
    )
    (net (code "120") (name "unconnected-(U1C-PD9-Pad78)") (class "Default")
      (node (ref "U1") (pin "78") (pinfunction "PD9_78") (pintype "bidirectional+no_connect"))
    )
    (net (code "121") (name "unconnected-(U1C-PD10-Pad79)") (class "Default")
      (node (ref "U1") (pin "79") (pinfunction "PD10_79") (pintype "bidirectional+no_connect"))
    )
    (net (code "122") (name "unconnected-(U1C-PDR_ON-Pad143)") (class "Default")
      (node (ref "U1") (pin "143") (pinfunction "PDR_ON_143") (pintype "power_in+no_connect"))
    )
    (net (code "123") (name "unconnected-(U1C-PF11-Pad49)") (class "Default")
      (node (ref "U1") (pin "49") (pinfunction "PF11_49") (pintype "bidirectional+no_connect"))
    )
    (net (code "124") (name "unconnected-(U1C-PH0-OSC_IN-Pad23)") (class "Default")
      (node (ref "U1") (pin "23") (pinfunction "PH0-OSC_IN_23") (pintype "bidirectional+no_connect"))
    )
    (net (code "125") (name "unconnected-(U1C-PH1-OSC_OUT-Pad24)") (class "Default")
      (node (ref "U1") (pin "24") (pinfunction "PH1-OSC_OUT_24") (pintype "bidirectional+no_connect"))
    )
  )
)
